# regulator.net
KiCad netlist of a schematic drawn in EAGLE
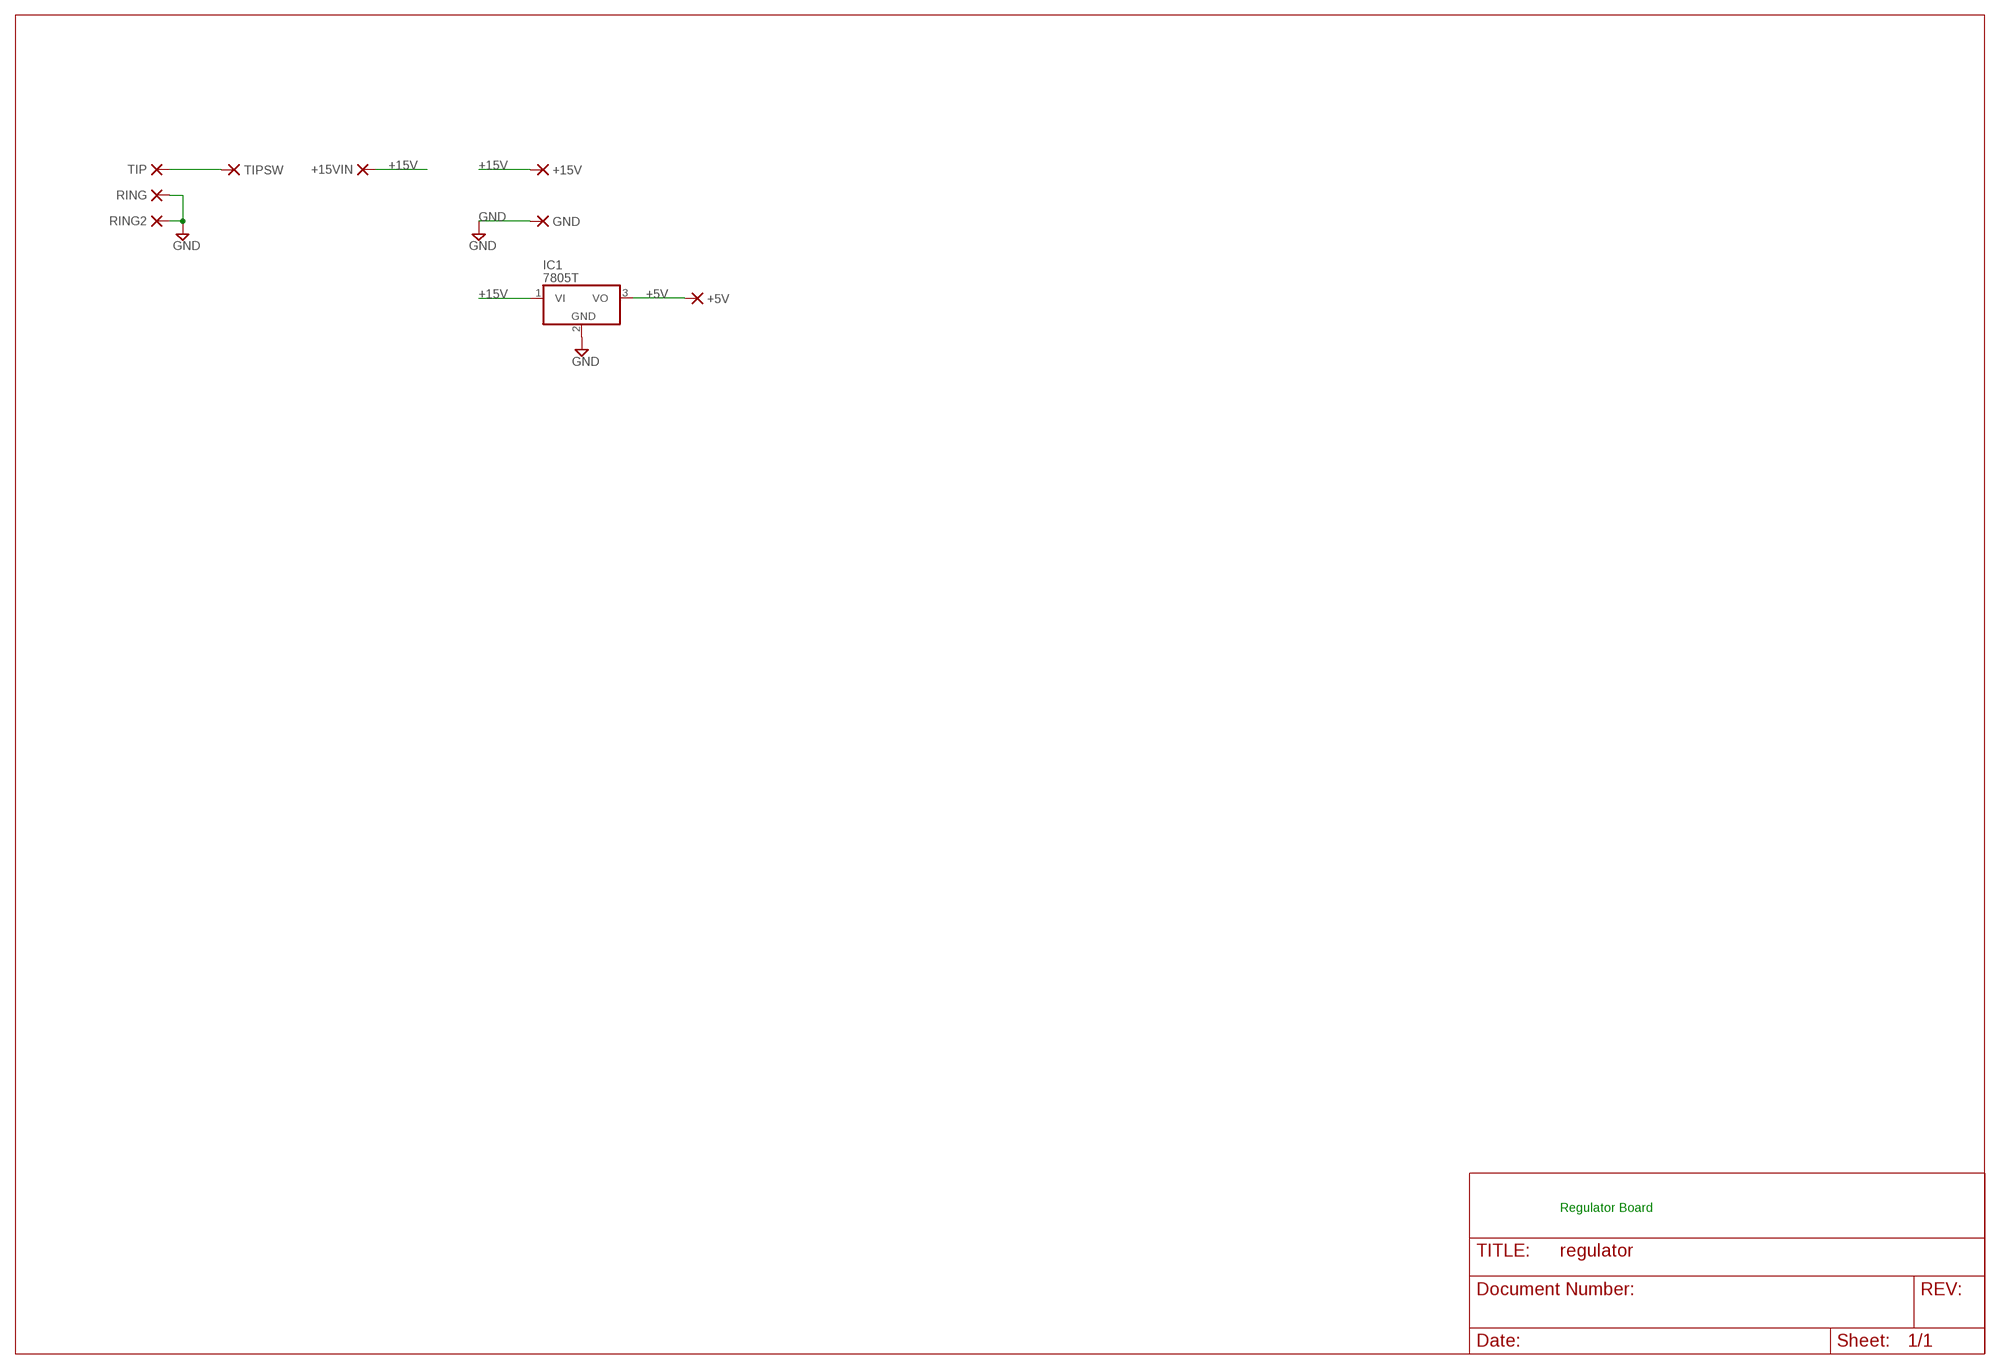
[diagram p0: schematic, sheet 1]

(export (version "E")
  (design (tool "Eeschema 10.0.6"))
  (components
    (comp (ref "+5V")
      (value "PAD-0635")
      (footprint "eagle-import:0635")
      (libsource (lib "eagle-import") (part "PAD-0635"))
    )
    (comp (ref "+15V")
      (value "PAD-0635")
      (footprint "eagle-import:0635")
      (libsource (lib "eagle-import") (part "PAD-0635"))
    )
    (comp (ref "+15VIN")
      (value "PAD-0635")
      (footprint "eagle-import:0635")
      (libsource (lib "eagle-import") (part "PAD-0635"))
    )
    (comp (ref "GND")
      (value "PAD-0635")
      (footprint "eagle-import:0635")
      (libsource (lib "eagle-import") (part "PAD-0635"))
    )
    (comp (ref "IC1")
      (value "7805T")
      (footprint "eagle-import:TO220H")
      (libsource (lib "eagle-import") (part "78T05"))
    )
    (comp (ref "RING")
      (value "PAD-0635")
      (footprint "eagle-import:0635")
      (libsource (lib "eagle-import") (part "PAD-0635"))
    )
    (comp (ref "RING2")
      (value "PAD-0635")
      (footprint "eagle-import:0635")
      (libsource (lib "eagle-import") (part "PAD-0635"))
    )
    (comp (ref "TIP")
      (value "PAD-0635")
      (footprint "eagle-import:0635")
      (libsource (lib "eagle-import") (part "PAD-0635"))
    )
    (comp (ref "TIPSW")
      (value "PAD-0635")
      (footprint "eagle-import:0635")
      (libsource (lib "eagle-import") (part "PAD-0635"))
    )
  )
  (nets
    (net (code "1") (name "/+5V") (class "Default")
      (node (ref "+5V") (pin "P$1") (pinfunction "P_P$1") (pintype "passive"))
      (node (ref "IC1") (pin "3") (pinfunction "VO_3") (pintype "passive"))
    )
    (net (code "2") (name "/+15V") (class "Default")
      (node (ref "+15V") (pin "P$1") (pinfunction "P_P$1") (pintype "passive"))
      (node (ref "+15VIN") (pin "P$1") (pinfunction "P_P$1") (pintype "passive"))
      (node (ref "IC1") (pin "1") (pinfunction "VI_1") (pintype "input"))
    )
    (net (code "3") (name "GND") (class "Default")
      (node (ref "GND") (pin "P$1") (pinfunction "P_P$1") (pintype "passive"))
      (node (ref "IC1") (pin "2") (pinfunction "GND_2") (pintype "passive"))
      (node (ref "RING") (pin "P$1") (pinfunction "P_P$1") (pintype "passive"))
      (node (ref "RING2") (pin "P$1") (pinfunction "P_P$1") (pintype "passive"))
    )
    (net (code "4") (name "Net-(TIP-P)") (class "Default")
      (node (ref "TIP") (pin "P$1") (pinfunction "P_P$1") (pintype "passive"))
      (node (ref "TIPSW") (pin "P$1") (pinfunction "P_P$1") (pintype "passive"))
    )
  )
)
